# MCU.net
KiCad netlist of a schematic drawn in Altium Designer
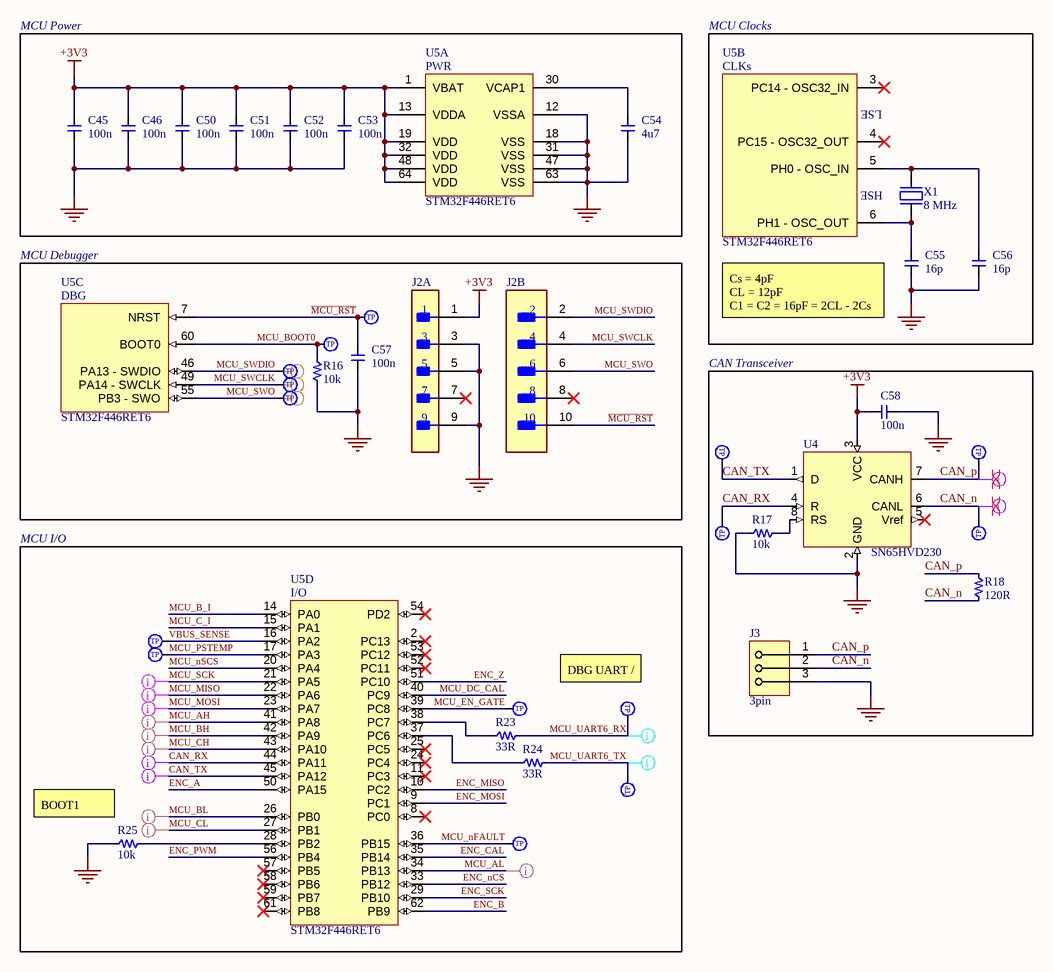
[diagram p0: MCU.SchDoc]

(export (version "E")
  (design (tool "Eeschema 10.0.6"))
  (components
    (comp (ref "C45")
      (value "100n")
      (footprint "C0402")
      (description "0402 cap")
      (libsource (lib "LinearDriver") (part "C_0402"))
    )
    (comp (ref "C46")
      (value "100n")
      (footprint "C0402")
      (description "0402 cap")
      (libsource (lib "LinearDriver") (part "C_0402"))
    )
    (comp (ref "C50")
      (value "100n")
      (footprint "C0402")
      (description "0402 cap")
      (libsource (lib "LinearDriver") (part "C_0402"))
    )
    (comp (ref "C51")
      (value "100n")
      (footprint "C0402")
      (description "0402 cap")
      (libsource (lib "LinearDriver") (part "C_0402"))
    )
    (comp (ref "C52")
      (value "100n")
      (footprint "C0402")
      (description "0402 cap")
      (libsource (lib "LinearDriver") (part "C_0402"))
    )
    (comp (ref "C53")
      (value "100n")
      (footprint "C0402")
      (description "0402 cap")
      (libsource (lib "LinearDriver") (part "C_0402"))
    )
    (comp (ref "C54")
      (value "4u7")
      (footprint "C0402")
      (description "0402 cap")
      (libsource (lib "LinearDriver") (part "C_0402"))
    )
    (comp (ref "C55")
      (value "16p")
      (footprint "C0402")
      (description "0402 cap")
      (libsource (lib "LinearDriver") (part "C_0402"))
    )
    (comp (ref "C56")
      (value "16p")
      (footprint "C0402")
      (description "0402 cap")
      (libsource (lib "LinearDriver") (part "C_0402"))
    )
    (comp (ref "C57")
      (value "100n")
      (footprint "C0402")
      (description "0402 cap")
      (libsource (lib "LinearDriver") (part "C_0402"))
    )
    (comp (ref "C58")
      (value "100n")
      (footprint "C0402")
      (description "0402 cap")
      (libsource (lib "LinearDriver") (part "C_0402"))
    )
    (comp (ref "J2")
      (value "FTSH-105-01-L-DV-K-TR")
      (footprint "FP-FTSH-105-01-L-DV-K-TR-MFG")
      (description "CONN HEADER SMD 10POS 1.27MM")
      (libsource (lib "Altium Content Vault") (part "cf1cfb4cb1e82ff90bf040e1afc05ac"))
    )
    (comp (ref "J3") (value "3pin") (footprint "3pin_ftp") (libsource (lib "R45_Driver") (part "3pin_ftp")))
    (comp (ref "R16")
      (value "10k")
      (footprint "R0402")
      (description "0402 62.5mW")
      (libsource (lib "LinearDriver") (part "R_0402"))
    )
    (comp (ref "R17")
      (value "10k")
      (footprint "R0402")
      (description "0402 62.5mW")
      (libsource (lib "LinearDriver") (part "R_0402"))
    )
    (comp (ref "R18")
      (value "120R")
      (footprint "R0603")
      (description "0603 100mW")
      (libsource (lib "R45_Driver") (part "R_0603"))
    )
    (comp (ref "R23")
      (value "33R")
      (footprint "R0402")
      (description "0402 62.5mW")
      (libsource (lib "LinearDriver") (part "R_0402"))
    )
    (comp (ref "R24")
      (value "33R")
      (footprint "R0402")
      (description "0402 62.5mW")
      (libsource (lib "LinearDriver") (part "R_0402"))
    )
    (comp (ref "R25")
      (value "10k")
      (footprint "R0402")
      (description "0402 62.5mW")
      (libsource (lib "LinearDriver") (part "R_0402"))
    )
    (comp (ref "TP14")
      (value "Testing_Point_1mm")
      (footprint "TestingPoint_1mm")
      (description "1mm testing point")
      (libsource (lib "LinearDriver") (part "Testing_Point_1mm"))
    )
    (comp (ref "TP15")
      (value "Testing_Point_1mm")
      (footprint "TestingPoint_1mm")
      (description "1mm testing point")
      (libsource (lib "LinearDriver") (part "Testing_Point_1mm"))
    )
    (comp (ref "TP16")
      (value "Testing_Point_1mm")
      (footprint "TestingPoint_1mm")
      (description "1mm testing point")
      (libsource (lib "LinearDriver") (part "Testing_Point_1mm"))
    )
    (comp (ref "TP17")
      (value "Testing_Point_1mm")
      (footprint "TestingPoint_1mm")
      (description "1mm testing point")
      (libsource (lib "LinearDriver") (part "Testing_Point_1mm"))
    )
    (comp (ref "TP18")
      (value "Testing_Point_1mm")
      (footprint "TestingPoint_1mm")
      (description "1mm testing point")
      (libsource (lib "LinearDriver") (part "Testing_Point_1mm"))
    )
    (comp (ref "TP19")
      (value "Testing_Point_1mm")
      (footprint "TestingPoint_1mm")
      (description "1mm testing point")
      (libsource (lib "LinearDriver") (part "Testing_Point_1mm"))
    )
    (comp (ref "TP20")
      (value "Testing_Point_1mm")
      (footprint "TestingPoint_1mm")
      (description "1mm testing point")
      (libsource (lib "LinearDriver") (part "Testing_Point_1mm"))
    )
    (comp (ref "TP21")
      (value "Testing_Point_1mm")
      (footprint "TestingPoint_1mm")
      (description "1mm testing point")
      (libsource (lib "LinearDriver") (part "Testing_Point_1mm"))
    )
    (comp (ref "TP22")
      (value "Testing_Point_1mm")
      (footprint "TestingPoint_1mm")
      (description "1mm testing point")
      (libsource (lib "LinearDriver") (part "Testing_Point_1mm"))
    )
    (comp (ref "TP25")
      (value "Testing_Point_1mm")
      (footprint "TestingPoint_1mm")
      (description "1mm testing point")
      (libsource (lib "LinearDriver") (part "Testing_Point_1mm"))
    )
    (comp (ref "TP26")
      (value "Testing_Point_1mm")
      (footprint "TestingPoint_1mm")
      (description "1mm testing point")
      (libsource (lib "LinearDriver") (part "Testing_Point_1mm"))
    )
    (comp (ref "TP33")
      (value "Testing_Point_1mm")
      (footprint "TestingPoint_1mm")
      (description "1mm testing point")
      (libsource (lib "LinearDriver") (part "Testing_Point_1mm"))
    )
    (comp (ref "TP34")
      (value "Testing_Point_1mm")
      (footprint "TestingPoint_1mm")
      (description "1mm testing point")
      (libsource (lib "LinearDriver") (part "Testing_Point_1mm"))
    )
    (comp (ref "TP41")
      (value "Testing_Point_1mm")
      (footprint "TestingPoint_1mm")
      (description "1mm testing point")
      (libsource (lib "LinearDriver") (part "Testing_Point_1mm"))
    )
    (comp (ref "TP44")
      (value "Testing_Point_1mm")
      (footprint "TestingPoint_1mm")
      (description "1mm testing point")
      (libsource (lib "LinearDriver") (part "Testing_Point_1mm"))
    )
    (comp (ref "U4")
      (value "SN65HVD230")
      (footprint "SOIC8_TI")
      (description "Interface Circuit, 1-Trnsvr, BICMOS, PDSO8")
      (fields
        (field (name "MANUFACTURER") "Texas Instruments")
        (field (name "MANUFACTURER PART NUMBER") "SN65HVD230DR")
      )
      (libsource (lib "drawers_v1.0") (part "SN65HVD230DR"))
    )
    (comp (ref "U5")
      (value "STM32F446RET6")
      (footprint "STM32 - LQFP64")
      (description "RISC Microcontroller, 32-Bit, FLASH, CORTEX-M4F CPU, 180MHz, CMOS, PQFP64")
      (fields (field (name "MANUFACTURER") "STMicroelectronics"))
      (libsource (lib "mother_Schlib") (part "STM32F446RET6"))
    )
    (comp (ref "X1")
      (value "8 MHz")
      (footprint "X_5032")
      (description "Crystals ECX-53 8.000 MHz 12 pF 5032 2 pad +/-20/30 ppm -40 +85 C 100O Max ESR")
      (fields
        (field (name "MANUFACTURER") "ECS International")
        (field (name "MANUFACTURER PART NUMBER") "ECS-80-12-30-JGN-TR")
      )
      (libsource (lib "mother_Schlib") (part "ECS-80-12-30-JGN-TR"))
    )
  )
  (nets
    (net (code "1") (name "+3V3") (class "Default")
      (node (ref "C45") (pin "2") (pinfunction "2_2") (pintype "passive"))
      (node (ref "C46") (pin "2") (pinfunction "2_2") (pintype "passive"))
      (node (ref "C50") (pin "2") (pinfunction "2_2") (pintype "passive"))
      (node (ref "C51") (pin "2") (pinfunction "2_2") (pintype "passive"))
      (node (ref "C52") (pin "2") (pinfunction "2_2") (pintype "passive"))
      (node (ref "C53") (pin "2") (pinfunction "2_2") (pintype "passive"))
      (node (ref "C58") (pin "2") (pinfunction "2_2") (pintype "passive"))
      (node (ref "J2") (pin "1") (pinfunction "1_1") (pintype "passive"))
      (node (ref "U4") (pin "3") (pinfunction "VCC_3") (pintype "input"))
      (node (ref "U5") (pin "1") (pinfunction "VBAT_1") (pintype "power_in"))
      (node (ref "U5") (pin "13") (pinfunction "VDDA_13") (pintype "power_in"))
      (node (ref "U5") (pin "19") (pinfunction "VDD_19") (pintype "power_in"))
      (node (ref "U5") (pin "32") (pinfunction "VDD_32") (pintype "power_in"))
      (node (ref "U5") (pin "48") (pinfunction "VDD_48") (pintype "power_in"))
      (node (ref "U5") (pin "64") (pinfunction "VDD_64") (pintype "power_in"))
    )
    (net (code "2") (name "/CAN_RX") (class "Default")
      (node (ref "TP21") (pin "1") (pinfunction "1_1") (pintype "passive"))
      (node (ref "U4") (pin "4") (pinfunction "R_4") (pintype "input"))
      (node (ref "U5") (pin "44") (pinfunction "PA11_44") (pintype "bidirectional"))
    )
    (net (code "3") (name "/CAN_TX") (class "Default")
      (node (ref "TP19") (pin "1") (pinfunction "1_1") (pintype "passive"))
      (node (ref "U4") (pin "1") (pinfunction "D_1") (pintype "output"))
      (node (ref "U5") (pin "45") (pinfunction "PA12_45") (pintype "bidirectional"))
    )
    (net (code "4") (name "/CAN_n") (class "Default")
      (node (ref "J3") (pin "2") (pinfunction "2_2") (pintype "passive"))
      (node (ref "R18") (pin "1") (pinfunction "1_1") (pintype "passive"))
      (node (ref "TP22") (pin "1") (pinfunction "1_1") (pintype "passive"))
      (node (ref "U4") (pin "6") (pinfunction "CANL_6") (pintype "bidirectional"))
    )
    (net (code "5") (name "/CAN_p") (class "Default")
      (node (ref "J3") (pin "1") (pinfunction "1_1") (pintype "passive"))
      (node (ref "R18") (pin "2") (pinfunction "2_2") (pintype "passive"))
      (node (ref "TP20") (pin "1") (pinfunction "1_1") (pintype "passive"))
      (node (ref "U4") (pin "7") (pinfunction "CANH_7") (pintype "bidirectional"))
    )
    (net (code "6") (name "/ENC_A") (class "Default")
      (node (ref "U5") (pin "50") (pinfunction "PA15_50") (pintype "bidirectional"))
    )
    (net (code "7") (name "/ENC_B") (class "Default")
      (node (ref "U5") (pin "62") (pinfunction "PB9_62") (pintype "bidirectional"))
    )
    (net (code "8") (name "/ENC_CAL") (class "Default")
      (node (ref "U5") (pin "35") (pinfunction "PB14_35") (pintype "bidirectional"))
    )
    (net (code "9") (name "/ENC_MISO") (class "Default")
      (node (ref "U5") (pin "10") (pinfunction "PC2_10") (pintype "bidirectional"))
    )
    (net (code "10") (name "/ENC_MOSI") (class "Default")
      (node (ref "U5") (pin "9") (pinfunction "PC1_9") (pintype "bidirectional"))
    )
    (net (code "11") (name "/ENC_PWM") (class "Default")
      (node (ref "U5") (pin "56") (pinfunction "PB4_56") (pintype "bidirectional"))
    )
    (net (code "12") (name "/ENC_SCK") (class "Default")
      (node (ref "U5") (pin "29") (pinfunction "PB10_29") (pintype "bidirectional"))
    )
    (net (code "13") (name "/ENC_Z") (class "Default")
      (node (ref "U5") (pin "51") (pinfunction "PC10_51") (pintype "bidirectional"))
    )
    (net (code "14") (name "/ENC_nCS") (class "Default")
      (node (ref "U5") (pin "33") (pinfunction "PB12_33") (pintype "bidirectional"))
    )
    (net (code "15") (name "/MCU_AH") (class "Default")
      (node (ref "U5") (pin "41") (pinfunction "PA8_41") (pintype "bidirectional"))
    )
    (net (code "16") (name "/MCU_AL") (class "Default")
      (node (ref "U5") (pin "34") (pinfunction "PB13_34") (pintype "bidirectional"))
    )
    (net (code "17") (name "/MCU_BH") (class "Default")
      (node (ref "U5") (pin "42") (pinfunction "PA9_42") (pintype "bidirectional"))
    )
    (net (code "18") (name "/MCU_BL") (class "Default")
      (node (ref "U5") (pin "26") (pinfunction "PB0_26") (pintype "bidirectional"))
    )
    (net (code "19") (name "/MCU_BOOT0") (class "Default")
      (node (ref "R16") (pin "1") (pinfunction "1_1") (pintype "passive"))
      (node (ref "TP15") (pin "1") (pinfunction "1_1") (pintype "passive"))
      (node (ref "U5") (pin "60") (pinfunction "BOOT0_60") (pintype "input"))
    )
    (net (code "20") (name "/MCU_B_I") (class "Default")
      (node (ref "U5") (pin "14") (pinfunction "PA0_14") (pintype "bidirectional"))
    )
    (net (code "21") (name "/MCU_CH") (class "Default")
      (node (ref "U5") (pin "43") (pinfunction "PA10_43") (pintype "bidirectional"))
    )
    (net (code "22") (name "/MCU_CL") (class "Default")
      (node (ref "U5") (pin "27") (pinfunction "PB1_27") (pintype "bidirectional"))
    )
    (net (code "23") (name "/MCU_C_I") (class "Default")
      (node (ref "U5") (pin "15") (pinfunction "PA1_15") (pintype "bidirectional"))
    )
    (net (code "24") (name "/MCU_DC_CAL") (class "Default")
      (node (ref "U5") (pin "40") (pinfunction "PC9_40") (pintype "bidirectional"))
    )
    (net (code "25") (name "/MCU_EN_GATE") (class "Default")
      (node (ref "TP33") (pin "1") (pinfunction "1_1") (pintype "passive"))
      (node (ref "U5") (pin "39") (pinfunction "PC8_39") (pintype "bidirectional"))
    )
    (net (code "26") (name "/MCU_MISO") (class "Default")
      (node (ref "U5") (pin "22") (pinfunction "PA6_22") (pintype "bidirectional"))
    )
    (net (code "27") (name "/MCU_MOSI") (class "Default")
      (node (ref "U5") (pin "23") (pinfunction "PA7_23") (pintype "bidirectional"))
    )
    (net (code "28") (name "/MCU_PSTEMP") (class "Default")
      (node (ref "TP26") (pin "1") (pinfunction "1_1") (pintype "passive"))
      (node (ref "U5") (pin "17") (pinfunction "PA3_17") (pintype "bidirectional"))
    )
    (net (code "29") (name "/MCU_RST") (class "Default")
      (node (ref "C57") (pin "2") (pinfunction "2_2") (pintype "passive"))
      (node (ref "J2") (pin "10") (pinfunction "10_10") (pintype "passive"))
      (node (ref "TP14") (pin "1") (pinfunction "1_1") (pintype "passive"))
      (node (ref "U5") (pin "7") (pinfunction "NRST_7") (pintype "input"))
    )
    (net (code "30") (name "/MCU_SCK") (class "Default")
      (node (ref "U5") (pin "21") (pinfunction "PA5_21") (pintype "bidirectional"))
    )
    (net (code "31") (name "/MCU_SWCLK") (class "Default")
      (node (ref "J2") (pin "4") (pinfunction "4_4") (pintype "passive"))
      (node (ref "TP17") (pin "1") (pinfunction "1_1") (pintype "passive"))
      (node (ref "U5") (pin "49") (pinfunction "PA14_-_SWCLK_49") (pintype "input"))
    )
    (net (code "32") (name "/MCU_SWDIO") (class "Default")
      (node (ref "J2") (pin "2") (pinfunction "2_2") (pintype "passive"))
      (node (ref "TP16") (pin "1") (pinfunction "1_1") (pintype "passive"))
      (node (ref "U5") (pin "46") (pinfunction "PA13_-_SWDIO_46") (pintype "bidirectional"))
    )
    (net (code "33") (name "/MCU_SWO") (class "Default")
      (node (ref "J2") (pin "6") (pinfunction "6_6") (pintype "passive"))
      (node (ref "TP18") (pin "1") (pinfunction "1_1") (pintype "passive"))
      (node (ref "U5") (pin "55") (pinfunction "PB3_-_SWO_55") (pintype "bidirectional"))
    )
    (net (code "34") (name "/MCU_UART6_RX") (class "Default")
      (node (ref "R23") (pin "2") (pinfunction "2_2") (pintype "passive"))
      (node (ref "TP34") (pin "1") (pinfunction "1_1") (pintype "passive"))
    )
    (net (code "35") (name "/MCU_UART6_TX") (class "Default")
      (node (ref "R24") (pin "2") (pinfunction "2_2") (pintype "passive"))
      (node (ref "TP41") (pin "1") (pinfunction "1_1") (pintype "passive"))
    )
    (net (code "36") (name "/MCU_nFAULT") (class "Default")
      (node (ref "TP44") (pin "1") (pinfunction "1_1") (pintype "passive"))
      (node (ref "U5") (pin "36") (pinfunction "PB15_36") (pintype "bidirectional"))
    )
    (net (code "37") (name "/MCU_nSCS") (class "Default")
      (node (ref "U5") (pin "20") (pinfunction "PA4_20") (pintype "bidirectional"))
    )
    (net (code "38") (name "/VBUS_SENSE") (class "Default")
      (node (ref "TP25") (pin "1") (pinfunction "1_1") (pintype "passive"))
      (node (ref "U5") (pin "16") (pinfunction "PA2_16") (pintype "bidirectional"))
    )
    (net (code "39") (name "GND") (class "Default")
      (node (ref "C45") (pin "1") (pinfunction "1_1") (pintype "passive"))
      (node (ref "C46") (pin "1") (pinfunction "1_1") (pintype "passive"))
      (node (ref "C50") (pin "1") (pinfunction "1_1") (pintype "passive"))
      (node (ref "C51") (pin "1") (pinfunction "1_1") (pintype "passive"))
      (node (ref "C52") (pin "1") (pinfunction "1_1") (pintype "passive"))
      (node (ref "C53") (pin "1") (pinfunction "1_1") (pintype "passive"))
      (node (ref "C54") (pin "1") (pinfunction "1_1") (pintype "passive"))
      (node (ref "C55") (pin "1") (pinfunction "1_1") (pintype "passive"))
      (node (ref "C56") (pin "1") (pinfunction "1_1") (pintype "passive"))
      (node (ref "C57") (pin "1") (pinfunction "1_1") (pintype "passive"))
      (node (ref "C58") (pin "1") (pinfunction "1_1") (pintype "passive"))
      (node (ref "J2") (pin "3") (pinfunction "3_3") (pintype "passive"))
      (node (ref "J2") (pin "5") (pinfunction "5_5") (pintype "passive"))
      (node (ref "J2") (pin "9") (pinfunction "9_9") (pintype "passive"))
      (node (ref "J3") (pin "3") (pinfunction "3_3") (pintype "passive"))
      (node (ref "R16") (pin "2") (pinfunction "2_2") (pintype "passive"))
      (node (ref "R17") (pin "1") (pinfunction "1_1") (pintype "passive"))
      (node (ref "R25") (pin "1") (pinfunction "1_1") (pintype "passive"))
      (node (ref "U4") (pin "2") (pinfunction "GND_2") (pintype "input"))
      (node (ref "U5") (pin "12") (pinfunction "VSSA_12") (pintype "power_in"))
      (node (ref "U5") (pin "18") (pinfunction "VSS_18") (pintype "power_in"))
      (node (ref "U5") (pin "31") (pinfunction "VSS_31") (pintype "power_in"))
      (node (ref "U5") (pin "47") (pinfunction "VSS_47") (pintype "power_in"))
      (node (ref "U5") (pin "63") (pinfunction "VSS_63") (pintype "power_in"))
    )
    (net (code "40") (name "Net-(U4-RS)") (class "Default")
      (node (ref "R17") (pin "2") (pinfunction "2_2") (pintype "passive"))
      (node (ref "U4") (pin "8") (pinfunction "RS_8") (pintype "input"))
    )
    (net (code "41") (name "Net-(U5A-VCAP1)") (class "Default")
      (node (ref "C54") (pin "2") (pinfunction "2_2") (pintype "passive"))
      (node (ref "U5") (pin "30") (pinfunction "VCAP1_30") (pintype "passive"))
    )
    (net (code "42") (name "Net-(U5B-PH0_-_OSC_IN)") (class "Default")
      (node (ref "C56") (pin "2") (pinfunction "2_2") (pintype "passive"))
      (node (ref "U5") (pin "5") (pinfunction "PH0_-_OSC_IN_5") (pintype "passive"))
      (node (ref "X1") (pin "2") (pinfunction "2_2") (pintype "passive"))
    )
    (net (code "43") (name "Net-(U5B-PH1_-_OSC_OUT)") (class "Default")
      (node (ref "C55") (pin "2") (pinfunction "2_2") (pintype "passive"))
      (node (ref "U5") (pin "6") (pinfunction "PH1_-_OSC_OUT_6") (pintype "passive"))
      (node (ref "X1") (pin "1") (pinfunction "1_1") (pintype "passive"))
    )
    (net (code "44") (name "Net-(U5D-PB2)") (class "Default")
      (node (ref "R25") (pin "2") (pinfunction "2_2") (pintype "passive"))
      (node (ref "U5") (pin "28") (pinfunction "PB2_28") (pintype "bidirectional"))
    )
    (net (code "45") (name "Net-(U5D-PC6)") (class "Default")
      (node (ref "R24") (pin "1") (pinfunction "1_1") (pintype "passive"))
      (node (ref "U5") (pin "37") (pinfunction "PC6_37") (pintype "bidirectional"))
    )
    (net (code "46") (name "Net-(U5D-PC7)") (class "Default")
      (node (ref "R23") (pin "1") (pinfunction "1_1") (pintype "passive"))
      (node (ref "U5") (pin "38") (pinfunction "PC7_38") (pintype "bidirectional"))
    )
    (net (code "47") (name "unconnected-(J2-Pad7)") (class "Default")
      (node (ref "J2") (pin "7") (pinfunction "7_7") (pintype "passive+no_connect"))
    )
    (net (code "48") (name "unconnected-(J2-Pad8)") (class "Default")
      (node (ref "J2") (pin "8") (pinfunction "8_8") (pintype "passive+no_connect"))
    )
    (net (code "49") (name "unconnected-(U4-Vref-Pad5)") (class "Default")
      (node (ref "U4") (pin "5") (pinfunction "Vref_5") (pintype "output+no_connect"))
    )
    (net (code "50") (name "unconnected-(U5B-PC14_-_OSC32_IN-Pad3)") (class "Default")
      (node (ref "U5") (pin "3") (pinfunction "PC14_-_OSC32_IN_3") (pintype "passive+no_connect"))
    )
    (net (code "51") (name "unconnected-(U5B-PC15_-_OSC32_OUT-Pad4)") (class "Default")
      (node (ref "U5") (pin "4") (pinfunction "PC15_-_OSC32_OUT_4") (pintype "passive+no_connect"))
    )
    (net (code "52") (name "unconnected-(U5D-PB5-Pad57)") (class "Default")
      (node (ref "U5") (pin "57") (pinfunction "PB5_57") (pintype "bidirectional+no_connect"))
    )
    (net (code "53") (name "unconnected-(U5D-PB6-Pad58)") (class "Default")
      (node (ref "U5") (pin "58") (pinfunction "PB6_58") (pintype "bidirectional+no_connect"))
    )
    (net (code "54") (name "unconnected-(U5D-PB7-Pad59)") (class "Default")
      (node (ref "U5") (pin "59") (pinfunction "PB7_59") (pintype "bidirectional+no_connect"))
    )
    (net (code "55") (name "unconnected-(U5D-PB8-Pad61)") (class "Default")
      (node (ref "U5") (pin "61") (pinfunction "PB8_61") (pintype "bidirectional+no_connect"))
    )
    (net (code "56") (name "unconnected-(U5D-PC0-Pad8)") (class "Default")
      (node (ref "U5") (pin "8") (pinfunction "PC0_8") (pintype "bidirectional+no_connect"))
    )
    (net (code "57") (name "unconnected-(U5D-PC3-Pad11)") (class "Default")
      (node (ref "U5") (pin "11") (pinfunction "PC3_11") (pintype "bidirectional+no_connect"))
    )
    (net (code "58") (name "unconnected-(U5D-PC4-Pad24)") (class "Default")
      (node (ref "U5") (pin "24") (pinfunction "PC4_24") (pintype "bidirectional+no_connect"))
    )
    (net (code "59") (name "unconnected-(U5D-PC5-Pad25)") (class "Default")
      (node (ref "U5") (pin "25") (pinfunction "PC5_25") (pintype "bidirectional+no_connect"))
    )
    (net (code "60") (name "unconnected-(U5D-PC11-Pad52)") (class "Default")
      (node (ref "U5") (pin "52") (pinfunction "PC11_52") (pintype "bidirectional+no_connect"))
    )
    (net (code "61") (name "unconnected-(U5D-PC12-Pad53)") (class "Default")
      (node (ref "U5") (pin "53") (pinfunction "PC12_53") (pintype "bidirectional+no_connect"))
    )
    (net (code "62") (name "unconnected-(U5D-PC13-Pad2)") (class "Default")
      (node (ref "U5") (pin "2") (pinfunction "PC13_2") (pintype "bidirectional+no_connect"))
    )
    (net (code "63") (name "unconnected-(U5D-PD2-Pad54)") (class "Default")
      (node (ref "U5") (pin "54") (pinfunction "PD2_54") (pintype "bidirectional+no_connect"))
    )
  )
)
